# schemat.net
KiCad netlist of a schematic drawn in Altium Designer
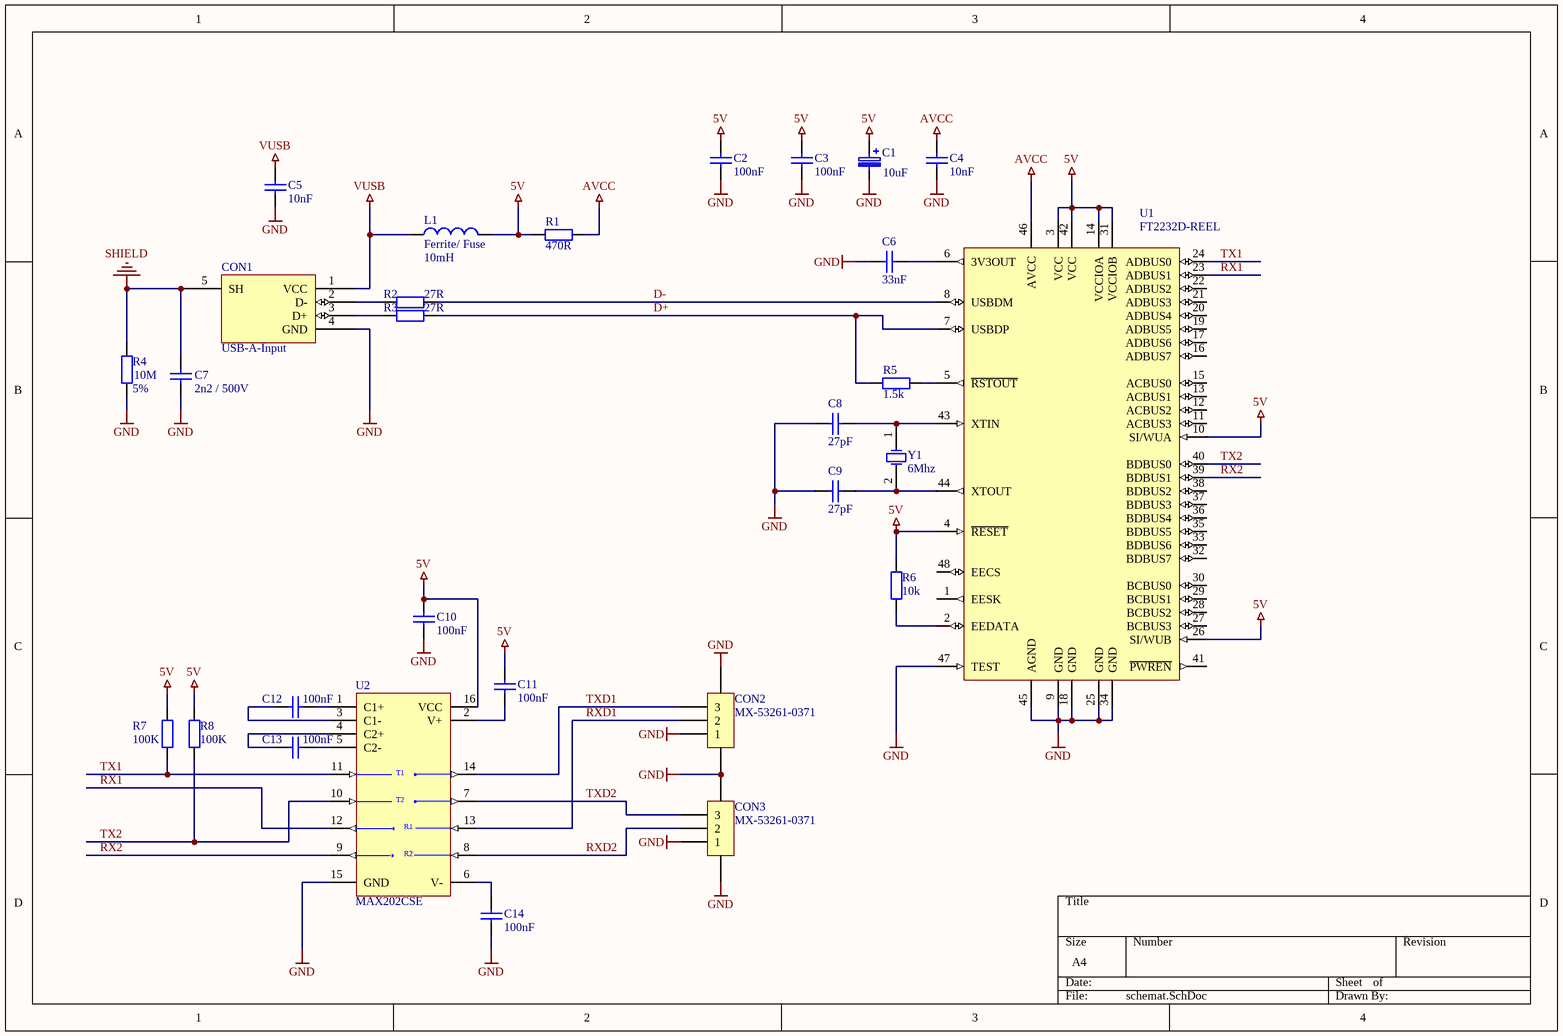
[diagram p0: schemat.SchDoc]

(export (version "E")
  (design (tool "Eeschema 10.0.6"))
  (components
    (comp (ref "C1")
      (value "10uF")
      (footprint "Mechatronic:SMDA")
      (description "Polarized Capacitor (Surface Mount)")
      (libsource (lib "Mechatronic") (part "100uF 6.3V-SMDB"))
    )
    (comp (ref "C2")
      (value "100nF")
      (footprint "CAPC1608N")
      (description "Capacitor")
      (libsource (lib "Discrete") (part "Capacitor"))
    )
    (comp (ref "C3")
      (value "100nF")
      (footprint "CAPC1608N")
      (description "Capacitor")
      (libsource (lib "Discrete") (part "Capacitor"))
    )
    (comp (ref "C4")
      (value "10nF")
      (footprint "CAPC1608N")
      (description "Capacitor")
      (libsource (lib "Discrete") (part "Capacitor"))
    )
    (comp (ref "C5")
      (value "10nF")
      (footprint "CAPC1608N")
      (description "Capacitor")
      (libsource (lib "Discrete") (part "Capacitor"))
    )
    (comp (ref "C6")
      (value "33nF")
      (footprint "CAPC1608N")
      (description "Capacitor")
      (libsource (lib "Discrete") (part "Capacitor"))
    )
    (comp (ref "C7")
      (value "2n2 / 500V")
      (footprint "CAPC3216N")
      (description "Capacitor")
      (libsource (lib "Discrete") (part "Capacitor"))
    )
    (comp (ref "C8")
      (value "27pF")
      (footprint "CAPC1608N")
      (description "Capacitor")
      (libsource (lib "Discrete") (part "Capacitor"))
    )
    (comp (ref "C9")
      (value "27pF")
      (footprint "CAPC1608N")
      (description "Capacitor")
      (libsource (lib "Discrete") (part "Capacitor"))
    )
    (comp (ref "C10")
      (value "100nF")
      (footprint "CAPC1608N")
      (description "Capacitor")
      (libsource (lib "Discrete") (part "Capacitor"))
    )
    (comp (ref "C11")
      (value "100nF")
      (footprint "CAPC1608N")
      (description "Capacitor")
      (libsource (lib "Discrete") (part "Capacitor"))
    )
    (comp (ref "C12")
      (value "100nF")
      (footprint "CAPC1608N")
      (description "Capacitor")
      (libsource (lib "Discrete") (part "Capacitor"))
    )
    (comp (ref "C13")
      (value "100nF")
      (footprint "CAPC1608N")
      (description "Capacitor")
      (libsource (lib "Discrete") (part "Capacitor"))
    )
    (comp (ref "C14")
      (value "100nF")
      (footprint "CAPC1608N")
      (description "Capacitor")
      (libsource (lib "Discrete") (part "Capacitor"))
    )
    (comp (ref "CON1")
      (value "USB-A-Input")
      (footprint "USB-A-input")
      (libsource (lib "my_various_devices") (part "USB-A-Input"))
    )
    (comp (ref "CON2")
      (value "MX-53261-0371")
      (footprint "MX-53261-0371")
      (description "Pitch 1.25mm, 3-pin")
      (libsource (lib "Connectors") (part "MX-53261-0371"))
    )
    (comp (ref "CON3")
      (value "MX-53261-0371")
      (footprint "MX-53261-0371")
      (description "Pitch 1.25mm, 3-pin")
      (libsource (lib "Connectors") (part "MX-53261-0371"))
    )
    (comp (ref "L1")
      (value "Ferrite/ Fuse")
      (footprint "FERRITE_1206")
      (description "Inductor")
      (fields (field (name "ALTIUM_VALUE") "10mH") (field (name "PUBLISHER") "Altium Limited"))
      (libsource (lib "Miscellaneous Devices") (part "Inductor"))
    )
    (comp (ref "R1")
      (value "470R")
      (footprint "Chip_Resistor_N:RESC1608N")
      (description "Resistor")
      (fields (field (name "TOLERANCE") "5%") (field (name "POWER") "0W"))
      (libsource (lib "Discrete") (part "Resistor"))
    )
    (comp (ref "R2")
      (value "27R")
      (footprint "Chip_Resistor_N:RESC1608N")
      (description "Resistor")
      (fields (field (name "TOLERANCE") "5%") (field (name "POWER") "0W"))
      (libsource (lib "") (part "Resistor_2"))
    )
    (comp (ref "R3")
      (value "27R")
      (footprint "Chip_Resistor_N:RESC1608N")
      (description "Resistor")
      (fields (field (name "TOLERANCE") "5%") (field (name "POWER") "0W"))
      (libsource (lib "") (part "Resistor_2"))
    )
    (comp (ref "R4")
      (value "10M")
      (footprint "RESC3216N")
      (description "Resistor")
      (fields (field (name "TOLERANCE") "5%") (field (name "POWER") "0W"))
      (libsource (lib "") (part "Resistor_1"))
    )
    (comp (ref "R5")
      (value "1.5k")
      (footprint "Chip_Resistor_N:RESC1608N")
      (description "Resistor")
      (fields (field (name "TOLERANCE") "5%") (field (name "POWER") "0W"))
      (libsource (lib "") (part "Resistor_2"))
    )
    (comp (ref "R6")
      (value "10k")
      (footprint "Chip_Resistor_N:RESC1608N")
      (description "Resistor")
      (fields (field (name "TOLERANCE") "5%") (field (name "POWER") "0W"))
      (libsource (lib "") (part "Resistor_1"))
    )
    (comp (ref "R7")
      (value "100K")
      (footprint "RESC1608N")
      (description "Resistor")
      (fields (field (name "POWER") "0W") (field (name "TOLERANCE") "5%"))
      (libsource (lib "") (part "Resistor_1"))
    )
    (comp (ref "R8")
      (value "100K")
      (footprint "RESC1608N")
      (description "Resistor")
      (fields (field (name "POWER") "0W") (field (name "TOLERANCE") "5%"))
      (libsource (lib "") (part "Resistor_1"))
    )
    (comp (ref "U1")
      (value "FT2232D-REEL")
      (footprint "LQFP-48_L")
      (description "FT2232D Dual USB to Serial UART/FIFO IC, -40 to +85 degC, 48-Pin LQFP, Pb-Free, Tape and Reel")
      (fields (field (name "MANUFACTURER") "FTDI"))
      (libsource (lib "my_various_devices") (part "COM-UART-FT2232D-SQ48"))
    )
    (comp (ref "U2")
      (value "MAX202CSE")
      (footprint "TI-D16_L")
      (description "+5V RS-232 Transceiver with 0.1µF External Capacitor")
      (fields (field (name "PUBLISHER") "Altium Limited"))
      (libsource (lib "Maxim Communication Transceiver") (part "MAX202CSE"))
    )
    (comp (ref "Y1")
      (value "6Mhz")
      (footprint "Discrete:HC-49U")
      (description "Crystal Oscillator")
      (libsource (lib "Discrete") (part "XTAL"))
    )
  )
  (nets
    (net (code "1") (name "/D+") (class "Default")
      (node (ref "R3") (pin "1") (pinfunction "1_1") (pintype "passive"))
      (node (ref "R5") (pin "2") (pinfunction "2_2") (pintype "passive"))
      (node (ref "U1") (pin "7") (pinfunction "USBDP_7") (pintype "bidirectional"))
    )
    (net (code "2") (name "/D-") (class "Default")
      (node (ref "R2") (pin "1") (pinfunction "1_1") (pintype "passive"))
      (node (ref "U1") (pin "8") (pinfunction "USBDM_8") (pintype "bidirectional"))
    )
    (net (code "3") (name "/RX1") (class "Default")
      (node (ref "U1") (pin "23") (pinfunction "ADBUS1_23") (pintype "bidirectional"))
      (node (ref "U2") (pin "12") (pinfunction "R1OUT_12") (pintype "output"))
    )
    (net (code "4") (name "/RX2") (class "Default")
      (node (ref "U1") (pin "39") (pinfunction "BDBUS1_39") (pintype "bidirectional"))
      (node (ref "U2") (pin "9") (pinfunction "R2OUT_9") (pintype "output"))
    )
    (net (code "5") (name "/RXD1") (class "Default")
      (node (ref "CON2") (pin "2") (pinfunction "2_2") (pintype "passive"))
      (node (ref "U2") (pin "13") (pinfunction "R1IN_13") (pintype "input"))
    )
    (net (code "6") (name "/RXD2") (class "Default")
      (node (ref "CON3") (pin "2") (pinfunction "2_2") (pintype "passive"))
      (node (ref "U2") (pin "8") (pinfunction "R2IN_8") (pintype "input"))
    )
    (net (code "7") (name "/TX1") (class "Default")
      (node (ref "R7") (pin "1") (pinfunction "1_1") (pintype "passive"))
      (node (ref "U1") (pin "24") (pinfunction "ADBUS0_24") (pintype "bidirectional"))
      (node (ref "U2") (pin "11") (pinfunction "T1IN_11") (pintype "input"))
    )
    (net (code "8") (name "/TX2") (class "Default")
      (node (ref "R8") (pin "1") (pinfunction "1_1") (pintype "passive"))
      (node (ref "U1") (pin "40") (pinfunction "BDBUS0_40") (pintype "bidirectional"))
      (node (ref "U2") (pin "10") (pinfunction "T2IN_10") (pintype "input"))
    )
    (net (code "9") (name "/TXD1") (class "Default")
      (node (ref "CON2") (pin "3") (pinfunction "3_3") (pintype "passive"))
      (node (ref "U2") (pin "14") (pinfunction "T1OUT_14") (pintype "output"))
    )
    (net (code "10") (name "/TXD2") (class "Default")
      (node (ref "CON3") (pin "3") (pinfunction "3_3") (pintype "passive"))
      (node (ref "U2") (pin "7") (pinfunction "T2OUT_7") (pintype "output"))
    )
    (net (code "11") (name "5V") (class "Default")
      (node (ref "C1") (pin "1") (pinfunction "1_1") (pintype "passive"))
      (node (ref "C10") (pin "2") (pinfunction "2_2") (pintype "passive"))
      (node (ref "C11") (pin "2") (pinfunction "2_2") (pintype "passive"))
      (node (ref "C2") (pin "2") (pinfunction "2_2") (pintype "passive"))
      (node (ref "C3") (pin "2") (pinfunction "2_2") (pintype "passive"))
      (node (ref "L1") (pin "2") (pinfunction "2_2") (pintype "passive"))
      (node (ref "R1") (pin "1") (pinfunction "1_1") (pintype "passive"))
      (node (ref "R6") (pin "2") (pinfunction "2_2") (pintype "passive"))
      (node (ref "R7") (pin "2") (pinfunction "2_2") (pintype "passive"))
      (node (ref "R8") (pin "2") (pinfunction "2_2") (pintype "passive"))
      (node (ref "U1") (pin "10") (pinfunction "SI/WUA_10") (pintype "input"))
      (node (ref "U1") (pin "14") (pinfunction "VCCIOA_14") (pintype "power_in"))
      (node (ref "U1") (pin "26") (pinfunction "SI/WUB_26") (pintype "input"))
      (node (ref "U1") (pin "3") (pinfunction "VCC_3") (pintype "power_in"))
      (node (ref "U1") (pin "31") (pinfunction "VCCIOB_31") (pintype "power_in"))
      (node (ref "U1") (pin "4") (pinfunction "~{RESET}_4") (pintype "input"))
      (node (ref "U1") (pin "42") (pinfunction "VCC_42") (pintype "power_in"))
      (node (ref "U2") (pin "16") (pinfunction "VCC_16") (pintype "power_in"))
    )
    (net (code "12") (name "AVCC") (class "Default")
      (node (ref "C4") (pin "1") (pinfunction "1_1") (pintype "passive"))
      (node (ref "R1") (pin "2") (pinfunction "2_2") (pintype "passive"))
      (node (ref "U1") (pin "46") (pinfunction "AVCC_46") (pintype "power_in"))
    )
    (net (code "13") (name "GND") (class "Default")
      (node (ref "C1") (pin "2") (pinfunction "2_2") (pintype "passive"))
      (node (ref "C10") (pin "1") (pinfunction "1_1") (pintype "passive"))
      (node (ref "C14") (pin "1") (pinfunction "1_1") (pintype "passive"))
      (node (ref "C2") (pin "1") (pinfunction "1_1") (pintype "passive"))
      (node (ref "C3") (pin "1") (pinfunction "1_1") (pintype "passive"))
      (node (ref "C4") (pin "2") (pinfunction "2_2") (pintype "passive"))
      (node (ref "C5") (pin "1") (pinfunction "1_1") (pintype "passive"))
      (node (ref "C6") (pin "2") (pinfunction "2_2") (pintype "passive"))
      (node (ref "C7") (pin "1") (pinfunction "1_1") (pintype "passive"))
      (node (ref "C8") (pin "2") (pinfunction "2_2") (pintype "passive"))
      (node (ref "C9") (pin "2") (pinfunction "2_2") (pintype "passive"))
      (node (ref "CON1") (pin "4") (pinfunction "GND_4") (pintype "power_in"))
      (node (ref "CON2") (pin "1") (pinfunction "1_1") (pintype "passive"))
      (node (ref "CON2") (pin "4") (pinfunction "4_4") (pintype "passive"))
      (node (ref "CON2") (pin "5") (pinfunction "5_5") (pintype "passive"))
      (node (ref "CON3") (pin "1") (pinfunction "1_1") (pintype "passive"))
      (node (ref "CON3") (pin "4") (pinfunction "4_4") (pintype "passive"))
      (node (ref "CON3") (pin "5") (pinfunction "5_5") (pintype "passive"))
      (node (ref "R4") (pin "1") (pinfunction "1_1") (pintype "passive"))
      (node (ref "U1") (pin "18") (pinfunction "GND_18") (pintype "power_in"))
      (node (ref "U1") (pin "25") (pinfunction "GND_25") (pintype "power_in"))
      (node (ref "U1") (pin "34") (pinfunction "GND_34") (pintype "power_in"))
      (node (ref "U1") (pin "45") (pinfunction "AGND_45") (pintype "power_in"))
      (node (ref "U1") (pin "47") (pinfunction "TEST_47") (pintype "input"))
      (node (ref "U1") (pin "9") (pinfunction "GND_9") (pintype "power_in"))
      (node (ref "U2") (pin "15") (pinfunction "GND_15") (pintype "power_in"))
    )
    (net (code "14") (name "Net-(CON1-D+)") (class "Default")
      (node (ref "CON1") (pin "3") (pinfunction "D+_3") (pintype "bidirectional"))
      (node (ref "R3") (pin "2") (pinfunction "2_2") (pintype "passive"))
    )
    (net (code "15") (name "Net-(CON1-D-)") (class "Default")
      (node (ref "CON1") (pin "2") (pinfunction "D-_2") (pintype "bidirectional"))
      (node (ref "R2") (pin "2") (pinfunction "2_2") (pintype "passive"))
    )
    (net (code "16") (name "Net-(U1-3V3OUT)") (class "Default")
      (node (ref "C6") (pin "1") (pinfunction "1_1") (pintype "passive"))
      (node (ref "U1") (pin "6") (pinfunction "3V3OUT_6") (pintype "output"))
    )
    (net (code "17") (name "Net-(U1-EEDATA)") (class "Default")
      (node (ref "R6") (pin "1") (pinfunction "1_1") (pintype "passive"))
      (node (ref "U1") (pin "2") (pinfunction "EEDATA_2") (pintype "bidirectional"))
    )
    (net (code "18") (name "Net-(U1-XTIN)") (class "Default")
      (node (ref "C8") (pin "1") (pinfunction "1_1") (pintype "passive"))
      (node (ref "U1") (pin "43") (pinfunction "XTIN_43") (pintype "input"))
      (node (ref "Y1") (pin "1") (pinfunction "OSC1_1") (pintype "passive"))
    )
    (net (code "19") (name "Net-(U1-XTOUT)") (class "Default")
      (node (ref "C9") (pin "1") (pinfunction "1_1") (pintype "passive"))
      (node (ref "U1") (pin "44") (pinfunction "XTOUT_44") (pintype "output"))
      (node (ref "Y1") (pin "2") (pinfunction "OSC2_2") (pintype "passive"))
    )
    (net (code "20") (name "Net-(U1-~{RSTOUT})") (class "Default")
      (node (ref "R5") (pin "1") (pinfunction "1_1") (pintype "passive"))
      (node (ref "U1") (pin "5") (pinfunction "~{RSTOUT}_5") (pintype "output"))
    )
    (net (code "21") (name "Net-(U2-C1+)") (class "Default")
      (node (ref "C12") (pin "2") (pinfunction "2_2") (pintype "passive"))
      (node (ref "U2") (pin "1") (pinfunction "C1+_1") (pintype "passive"))
    )
    (net (code "22") (name "Net-(U2-C1-)") (class "Default")
      (node (ref "C12") (pin "1") (pinfunction "1_1") (pintype "passive"))
      (node (ref "U2") (pin "3") (pinfunction "C1-_3") (pintype "passive"))
    )
    (net (code "23") (name "Net-(U2-C2+)") (class "Default")
      (node (ref "C13") (pin "1") (pinfunction "1_1") (pintype "passive"))
      (node (ref "U2") (pin "4") (pinfunction "C2+_4") (pintype "passive"))
    )
    (net (code "24") (name "Net-(U2-C2-)") (class "Default")
      (node (ref "C13") (pin "2") (pinfunction "2_2") (pintype "passive"))
      (node (ref "U2") (pin "5") (pinfunction "C2-_5") (pintype "passive"))
    )
    (net (code "25") (name "Net-(U2-V+)") (class "Default")
      (node (ref "C11") (pin "1") (pinfunction "1_1") (pintype "passive"))
      (node (ref "U2") (pin "2") (pinfunction "V+_2") (pintype "power_in"))
    )
    (net (code "26") (name "Net-(U2-V-)") (class "Default")
      (node (ref "C14") (pin "2") (pinfunction "2_2") (pintype "passive"))
      (node (ref "U2") (pin "6") (pinfunction "V-_6") (pintype "power_in"))
    )
    (net (code "27") (name "SHIELD") (class "Default")
      (node (ref "C7") (pin "2") (pinfunction "2_2") (pintype "passive"))
      (node (ref "CON1") (pin "5") (pinfunction "SH_5") (pintype "passive"))
      (node (ref "R4") (pin "2") (pinfunction "2_2") (pintype "passive"))
    )
    (net (code "28") (name "VUSB") (class "Default")
      (node (ref "C5") (pin "2") (pinfunction "2_2") (pintype "passive"))
      (node (ref "CON1") (pin "1") (pinfunction "VCC_1") (pintype "power_in"))
      (node (ref "L1") (pin "1") (pinfunction "1_1") (pintype "passive"))
    )
    (net (code "29") (name "unconnected-(U1-ACBUS0-Pad15)") (class "Default")
      (node (ref "U1") (pin "15") (pinfunction "ACBUS0_15") (pintype "bidirectional"))
    )
    (net (code "30") (name "unconnected-(U1-ACBUS1-Pad13)") (class "Default")
      (node (ref "U1") (pin "13") (pinfunction "ACBUS1_13") (pintype "bidirectional"))
    )
    (net (code "31") (name "unconnected-(U1-ACBUS2-Pad12)") (class "Default")
      (node (ref "U1") (pin "12") (pinfunction "ACBUS2_12") (pintype "bidirectional"))
    )
    (net (code "32") (name "unconnected-(U1-ACBUS3-Pad11)") (class "Default")
      (node (ref "U1") (pin "11") (pinfunction "ACBUS3_11") (pintype "bidirectional"))
    )
    (net (code "33") (name "unconnected-(U1-ADBUS2-Pad22)") (class "Default")
      (node (ref "U1") (pin "22") (pinfunction "ADBUS2_22") (pintype "bidirectional"))
    )
    (net (code "34") (name "unconnected-(U1-ADBUS3-Pad21)") (class "Default")
      (node (ref "U1") (pin "21") (pinfunction "ADBUS3_21") (pintype "bidirectional"))
    )
    (net (code "35") (name "unconnected-(U1-ADBUS4-Pad20)") (class "Default")
      (node (ref "U1") (pin "20") (pinfunction "ADBUS4_20") (pintype "bidirectional"))
    )
    (net (code "36") (name "unconnected-(U1-ADBUS5-Pad19)") (class "Default")
      (node (ref "U1") (pin "19") (pinfunction "ADBUS5_19") (pintype "bidirectional"))
    )
    (net (code "37") (name "unconnected-(U1-ADBUS6-Pad17)") (class "Default")
      (node (ref "U1") (pin "17") (pinfunction "ADBUS6_17") (pintype "bidirectional"))
    )
    (net (code "38") (name "unconnected-(U1-ADBUS7-Pad16)") (class "Default")
      (node (ref "U1") (pin "16") (pinfunction "ADBUS7_16") (pintype "bidirectional"))
    )
    (net (code "39") (name "unconnected-(U1-BCBUS0-Pad30)") (class "Default")
      (node (ref "U1") (pin "30") (pinfunction "BCBUS0_30") (pintype "bidirectional"))
    )
    (net (code "40") (name "unconnected-(U1-BCBUS1-Pad29)") (class "Default")
      (node (ref "U1") (pin "29") (pinfunction "BCBUS1_29") (pintype "bidirectional"))
    )
    (net (code "41") (name "unconnected-(U1-BCBUS2-Pad28)") (class "Default")
      (node (ref "U1") (pin "28") (pinfunction "BCBUS2_28") (pintype "bidirectional"))
    )
    (net (code "42") (name "unconnected-(U1-BCBUS3-Pad27)") (class "Default")
      (node (ref "U1") (pin "27") (pinfunction "BCBUS3_27") (pintype "bidirectional"))
    )
    (net (code "43") (name "unconnected-(U1-BDBUS2-Pad38)") (class "Default")
      (node (ref "U1") (pin "38") (pinfunction "BDBUS2_38") (pintype "bidirectional"))
    )
    (net (code "44") (name "unconnected-(U1-BDBUS3-Pad37)") (class "Default")
      (node (ref "U1") (pin "37") (pinfunction "BDBUS3_37") (pintype "bidirectional"))
    )
    (net (code "45") (name "unconnected-(U1-BDBUS4-Pad36)") (class "Default")
      (node (ref "U1") (pin "36") (pinfunction "BDBUS4_36") (pintype "bidirectional"))
    )
    (net (code "46") (name "unconnected-(U1-BDBUS5-Pad35)") (class "Default")
      (node (ref "U1") (pin "35") (pinfunction "BDBUS5_35") (pintype "bidirectional"))
    )
    (net (code "47") (name "unconnected-(U1-BDBUS6-Pad33)") (class "Default")
      (node (ref "U1") (pin "33") (pinfunction "BDBUS6_33") (pintype "bidirectional"))
    )
    (net (code "48") (name "unconnected-(U1-BDBUS7-Pad32)") (class "Default")
      (node (ref "U1") (pin "32") (pinfunction "BDBUS7_32") (pintype "bidirectional"))
    )
    (net (code "49") (name "unconnected-(U1-EECS-Pad48)") (class "Default")
      (node (ref "U1") (pin "48") (pinfunction "EECS_48") (pintype "bidirectional"))
    )
    (net (code "50") (name "unconnected-(U1-EESK-Pad1)") (class "Default")
      (node (ref "U1") (pin "1") (pinfunction "EESK_1") (pintype "output"))
    )
    (net (code "51") (name "unconnected-(U1-~{PWREN}-Pad41)") (class "Default")
      (node (ref "U1") (pin "41") (pinfunction "~{PWREN}_41") (pintype "output"))
    )
  )
)
